# Microcontroller.net
KiCad netlist of a schematic drawn in Altium Designer
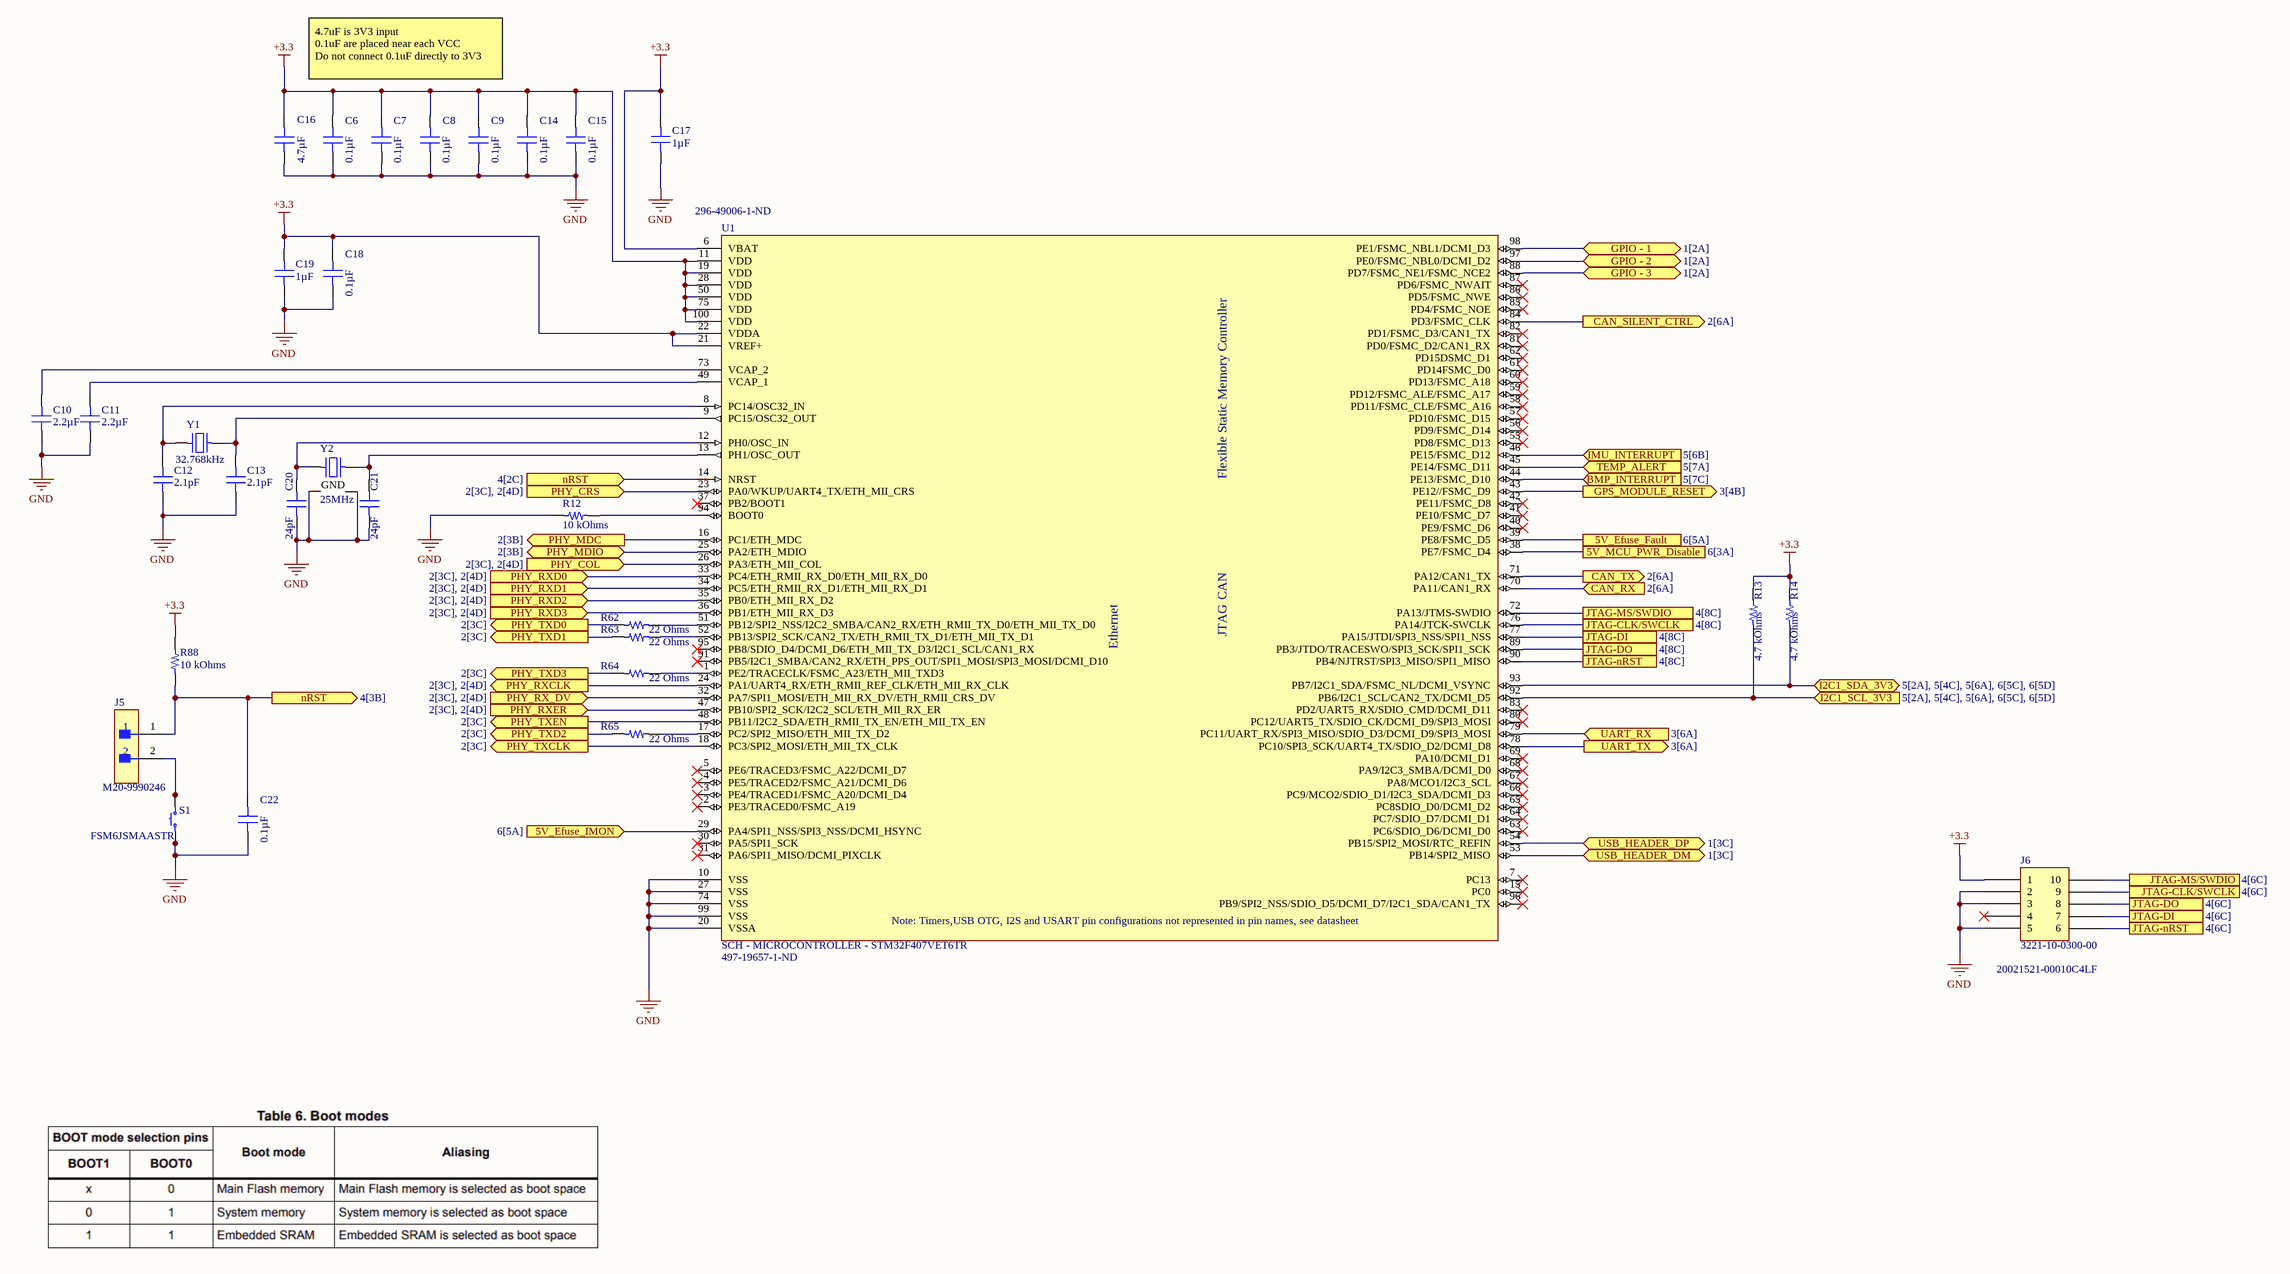
[diagram p0: Microcontroller.SchDoc]

(export (version "E")
  (design (tool "Eeschema 10.0.6"))
  (components
    (comp (ref "C6")
      (value "0.1µF")
      (footprint "CAP 0603_1608")
      (description "CAP CER 0.1UF 25V X7R 0603")
      (fields
        (field (name "PART NUMBER") "CL10B104KA8WPNC")
        (field (name "MANUFACTURER") "Samsung Electro-Mechanics")
      )
      (libsource (lib "Celestial Altium Library - altium_library") (part "Capacitor"))
    )
    (comp (ref "C7")
      (value "0.1µF")
      (footprint "CAP 0603_1608")
      (description "CAP CER 0.1UF 25V X7R 0603")
      (fields
        (field (name "PART NUMBER") "CL10B104KA8WPNC")
        (field (name "MANUFACTURER") "Samsung Electro-Mechanics")
      )
      (libsource (lib "Celestial Altium Library - altium_library") (part "Capacitor"))
    )
    (comp (ref "C8")
      (value "0.1µF")
      (footprint "CAP 0603_1608")
      (description "CAP CER 0.1UF 25V X7R 0603")
      (fields
        (field (name "PART NUMBER") "CL10B104KA8WPNC")
        (field (name "MANUFACTURER") "Samsung Electro-Mechanics")
      )
      (libsource (lib "Celestial Altium Library - altium_library") (part "Capacitor"))
    )
    (comp (ref "C9")
      (value "0.1µF")
      (footprint "CAP 0603_1608")
      (description "CAP CER 0.1UF 25V X7R 0603")
      (fields
        (field (name "PART NUMBER") "CL10B104KA8WPNC")
        (field (name "MANUFACTURER") "Samsung Electro-Mechanics")
      )
      (libsource (lib "Celestial Altium Library - altium_library") (part "Capacitor"))
    )
    (comp (ref "C10")
      (value "2.2µF")
      (footprint "CAP 0603_1608")
      (description "CAP CER 2.2UF 16V X5R 0603")
      (fields (field (name "PART NUMBER") "EMK107BJ225KA-T") (field (name "MANUFACTURER") "Taiyo Yuden"))
      (libsource (lib "Celestial Altium Library - altium_library") (part "Capacitor"))
    )
    (comp (ref "C11")
      (value "2.2µF")
      (footprint "CAP 0603_1608")
      (description "CAP CER 2.2UF 16V X5R 0603")
      (fields (field (name "PART NUMBER") "EMK107BJ225KA-T") (field (name "MANUFACTURER") "Taiyo Yuden"))
      (libsource (lib "Celestial Altium Library - altium_library") (part "Capacitor"))
    )
    (comp (ref "C12")
      (value "2.1pF")
      (footprint "CAP 0603_1608")
      (description "CAP CER RF 2.1PF 50V +/-0.1 PF C")
      (fields (field (name "PART NUMBER") "CBR06C219B5GAC") (field (name "MANUFACTURER") "KEMET"))
      (libsource (lib "Celestial Altium Library - altium_library") (part "Capacitor"))
    )
    (comp (ref "C13")
      (value "2.1pF")
      (footprint "CAP 0603_1608")
      (description "CAP CER RF 2.1PF 50V +/-0.1 PF C")
      (fields (field (name "PART NUMBER") "CBR06C219B5GAC") (field (name "MANUFACTURER") "KEMET"))
      (libsource (lib "Celestial Altium Library - altium_library") (part "Capacitor"))
    )
    (comp (ref "C14")
      (value "0.1µF")
      (footprint "CAP 0603_1608")
      (description "CAP CER 0.1UF 25V X7R 0603")
      (fields
        (field (name "PART NUMBER") "CL10B104KA8WPNC")
        (field (name "MANUFACTURER") "Samsung Electro-Mechanics")
      )
      (libsource (lib "Celestial Altium Library - altium_library") (part "Capacitor"))
    )
    (comp (ref "C15")
      (value "0.1µF")
      (footprint "CAP 0603_1608")
      (description "CAP CER 0.1UF 25V X7R 0603")
      (fields
        (field (name "PART NUMBER") "CL10B104KA8WPNC")
        (field (name "MANUFACTURER") "Samsung Electro-Mechanics")
      )
      (libsource (lib "Celestial Altium Library - altium_library") (part "Capacitor"))
    )
    (comp (ref "C16")
      (value "4.7µF")
      (footprint "CAP 0603_1608")
      (description "CAP CER 4.7UF 16V X5R 0603")
      (fields
        (field (name "PART NUMBER") "C1608X5R1C475K080AC")
        (field (name "MANUFACTURER") "TDK Corporation")
      )
      (libsource (lib "Celestial Altium Library - altium_library") (part "Capacitor"))
    )
    (comp (ref "C17")
      (value "1µF")
      (footprint "CAP 0603_1608")
      (description "CAP CER 1UF 16V X7R 0603")
      (fields
        (field (name "PART NUMBER") "GCM188R71C105KA64J")
        (field (name "MANUFACTURER") "Murata Electronics")
      )
      (libsource (lib "Celestial Altium Library - altium_library") (part "Capacitor"))
    )
    (comp (ref "C18")
      (value "0.1µF")
      (footprint "CAP 0603_1608")
      (description "CAP CER 0.1UF 25V X7R 0603")
      (fields
        (field (name "PART NUMBER") "CL10B104KA8WPNC")
        (field (name "MANUFACTURER") "Samsung Electro-Mechanics")
      )
      (libsource (lib "Celestial Altium Library - altium_library") (part "Capacitor"))
    )
    (comp (ref "C19")
      (value "1µF")
      (footprint "CAP 0603_1608")
      (description "CAP CER 1UF 16V X7R 0603")
      (fields
        (field (name "PART NUMBER") "GCM188R71C105KA64J")
        (field (name "MANUFACTURER") "Murata Electronics")
      )
      (libsource (lib "Celestial Altium Library - altium_library") (part "Capacitor"))
    )
    (comp (ref "C20")
      (value "24pF")
      (footprint "CAP 0603_1608")
      (description "CAP CER 24PF 50V C0G/NP0 0603")
      (fields
        (field (name "PART NUMBER") "CL10C240JB8NNNC")
        (field (name "MANUFACTURER") "Samsung Electro-Mechanics")
      )
      (libsource (lib "Celestial Altium Library - altium_library") (part "Capacitor"))
    )
    (comp (ref "C21")
      (value "24pF")
      (footprint "CAP 0603_1608")
      (description "CAP CER 24PF 50V C0G/NP0 0603")
      (fields
        (field (name "PART NUMBER") "CL10C240JB8NNNC")
        (field (name "MANUFACTURER") "Samsung Electro-Mechanics")
      )
      (libsource (lib "Celestial Altium Library - altium_library") (part "Capacitor"))
    )
    (comp (ref "C22")
      (value "0.1µF")
      (footprint "CAP 0603_1608")
      (description "CAP CER 0.1UF 25V X7R 0603")
      (fields
        (field (name "PART NUMBER") "CL10B104KA8WPNC")
        (field (name "MANUFACTURER") "Samsung Electro-Mechanics")
      )
      (libsource (lib "Celestial Altium Library - altium_library") (part "Capacitor"))
    )
    (comp (ref "J5")
      (value "M20-9990246")
      (footprint "FP-M20-9990246-MFG")
      (description "CONN HEADER VERT 2POS 2.54MM")
      (fields
        (field (name "OCTOPART") "https://octopart.com/m20-9990246-harwin-2590635")
        (field (name "MANUFACTURER") "Harwin")
      )
      (libsource (lib "Altium Content Vault") (part "3bc925449376181038e59eaffc5286c"))
    )
    (comp (ref "J6")
      (value "3221-10-0300-00")
      (footprint "CNC TECH 3221-10-0300-00")
      (description "CONN HEADER SMD 10POS 1.27MM")
      (fields (field (name "MANUFACTURER") "CNC Tech"))
      (libsource (lib "Celestial Altium Library - altium_library") (part "2x5 Pin"))
    )
    (comp (ref "R12")
      (value "10 kOhms")
      (footprint "RES 0603_1608")
      (description "RES 10K OHM 5% 1/10W 0603")
      (fields
        (field (name "PART NUMBER") "RMCF0603JT10K0")
        (field (name "MANUFACTURER") "Stackpole Electronics Inc")
      )
      (libsource (lib "Celestial Altium Library - altium_library") (part "Resistor"))
    )
    (comp (ref "R13")
      (value "4.7 kOhms")
      (footprint "RES 0603_1608")
      (description "RES 4.7K OHM 1% 1/10W 0603")
      (fields
        (field (name "PART NUMBER") "RMCF0603FT4K70")
        (field (name "MANUFACTURER") "Stackpole Electronics Inc")
      )
      (libsource (lib "Celestial Altium Library - altium_library") (part "Resistor"))
    )
    (comp (ref "R14")
      (value "4.7 kOhms")
      (footprint "RES 0603_1608")
      (description "RES 4.7K OHM 1% 1/10W 0603")
      (fields
        (field (name "PART NUMBER") "RMCF0603FT4K70")
        (field (name "MANUFACTURER") "Stackpole Electronics Inc")
      )
      (libsource (lib "Celestial Altium Library - altium_library") (part "Resistor"))
    )
    (comp (ref "R62")
      (value "22 Ohms")
      (footprint "RES 0603_1608")
      (description "RES 22 OHM 1% 1/10W 0603")
      (fields
        (field (name "PART NUMBER") "RMCF0603FT22R0")
        (field (name "MANUFACTURER") "Stackpole Electronics Inc")
      )
      (libsource (lib "Celestial Altium Library - altium_library") (part "Resistor"))
    )
    (comp (ref "R63")
      (value "22 Ohms")
      (footprint "RES 0603_1608")
      (description "RES 22 OHM 1% 1/10W 0603")
      (fields
        (field (name "PART NUMBER") "RMCF0603FT22R0")
        (field (name "MANUFACTURER") "Stackpole Electronics Inc")
      )
      (libsource (lib "Celestial Altium Library - altium_library") (part "Resistor"))
    )
    (comp (ref "R64")
      (value "22 Ohms")
      (footprint "RES 0603_1608")
      (description "RES 22 OHM 1% 1/10W 0603")
      (fields
        (field (name "PART NUMBER") "RMCF0603FT22R0")
        (field (name "MANUFACTURER") "Stackpole Electronics Inc")
      )
      (libsource (lib "Celestial Altium Library - altium_library") (part "Resistor"))
    )
    (comp (ref "R65")
      (value "22 Ohms")
      (footprint "RES 0603_1608")
      (description "RES 22 OHM 1% 1/10W 0603")
      (fields
        (field (name "PART NUMBER") "RMCF0603FT22R0")
        (field (name "MANUFACTURER") "Stackpole Electronics Inc")
      )
      (libsource (lib "Celestial Altium Library - altium_library") (part "Resistor"))
    )
    (comp (ref "R88")
      (value "10 kOhms")
      (footprint "RES 0603_1608")
      (description "RES 10K OHM 5% 1/10W 0603")
      (fields
        (field (name "PART NUMBER") "RMCF0603JT10K0")
        (field (name "MANUFACTURER") "Stackpole Electronics Inc")
      )
      (libsource (lib "Celestial Altium Library - altium_library") (part "Resistor"))
    )
    (comp (ref "S1")
      (value "FSM6JSMAASTR")
      (footprint "TE FSM6JSMA")
      (description "SWITCH TACTILE SPST-NO 0.05A 24V")
      (fields (field (name "MANUFACTURER") "TE Connectivity ALCOSWITCH Switches"))
      (libsource (lib "Celestial Altium Library - altium_library") (part "SPST-NO 4 PIN"))
    )
    (comp (ref "U1")
      (value "SCH - MICROCONTROLLER - STM32F407VET6TR")
      (footprint "PCB - LEADLESS - QFP - ST LQFP-100 14X14MM")
      (fields (field (name "SUPPLIER PART NUMBER 1") "497-19657-1-ND"))
      (libsource (lib "HAB_ICs") (part "SCH - MICROCONTROLLER - STM32F407VET6TR"))
    )
    (comp (ref "Y1")
      (value "32.768kHz")
      (footprint "ABRACON ABS07")
      (description "IOT 32.786KHZ XTAL")
      (fields
        (field (name "PART NUMBER") "ABS07-166-32.768KHZ-T")
        (field (name "MANUFACTURER") "Abracon LLC")
      )
      (libsource (lib "Celestial Altium Library - altium_library") (part "Abracon Crystal ABS07"))
    )
    (comp (ref "Y2")
      (value "25MHz")
      (footprint "EPSON TSX-3225")
      (description "CRYSTAL 25.0000MHZ 18PF SMD")
      (fields (field (name "PART NUMBER") "TSX-3225 25.0000MF20P-C0") (field (name "MANUFACTURER") "EPSON"))
      (libsource (lib "Celestial Altium Library - altium_library") (part "Epson Crystal TSX-3225"))
    )
  )
  (nets
    (net (code "1") (name "+3.3") (class "Default")
      (node (ref "C14") (pin "2") (pinfunction "2_2") (pintype "passive"))
      (node (ref "C15") (pin "2") (pinfunction "2_2") (pintype "passive"))
      (node (ref "C16") (pin "2") (pinfunction "2_2") (pintype "passive"))
      (node (ref "C17") (pin "2") (pinfunction "2_2") (pintype "passive"))
      (node (ref "C18") (pin "2") (pinfunction "2_2") (pintype "passive"))
      (node (ref "C19") (pin "2") (pinfunction "2_2") (pintype "passive"))
      (node (ref "C6") (pin "2") (pinfunction "2_2") (pintype "passive"))
      (node (ref "C7") (pin "2") (pinfunction "2_2") (pintype "passive"))
      (node (ref "C8") (pin "2") (pinfunction "2_2") (pintype "passive"))
      (node (ref "C9") (pin "2") (pinfunction "2_2") (pintype "passive"))
      (node (ref "J6") (pin "1") (pinfunction "1_1") (pintype "passive"))
      (node (ref "R13") (pin "2") (pinfunction "2_2") (pintype "passive"))
      (node (ref "R14") (pin "2") (pinfunction "2_2") (pintype "passive"))
      (node (ref "R88") (pin "1") (pinfunction "1_1") (pintype "passive"))
      (node (ref "U1") (pin "100") (pinfunction "VDD_100") (pintype "power_in"))
      (node (ref "U1") (pin "11") (pinfunction "VDD_11") (pintype "power_in"))
      (node (ref "U1") (pin "19") (pinfunction "VDD_19") (pintype "power_in"))
      (node (ref "U1") (pin "21") (pinfunction "VREF+_21") (pintype "power_in"))
      (node (ref "U1") (pin "22") (pinfunction "VDDA_22") (pintype "power_in"))
      (node (ref "U1") (pin "28") (pinfunction "VDD_28") (pintype "power_in"))
      (node (ref "U1") (pin "50") (pinfunction "VDD_50") (pintype "power_in"))
      (node (ref "U1") (pin "6") (pinfunction "VBAT_6") (pintype "power_in"))
      (node (ref "U1") (pin "75") (pinfunction "VDD_75") (pintype "power_in"))
    )
    (net (code "2") (name "/5V_Efuse_Fault") (class "Default")
      (node (ref "U1") (pin "39") (pinfunction "PE8/FSMC_D5_39") (pintype "bidirectional"))
    )
    (net (code "3") (name "/5V_Efuse_IMON") (class "Default")
      (node (ref "U1") (pin "29") (pinfunction "PA4/SPI1_NSS/SPI3_NSS/DCMI_HSYNC_29") (pintype "bidirectional"))
    )
    (net (code "4") (name "/5V_MCU_PWR_Disable") (class "Default")
      (node (ref "U1") (pin "38") (pinfunction "PE7/FSMC_D4_38") (pintype "bidirectional"))
    )
    (net (code "5") (name "/BMP_INTERRUPT") (class "Default")
      (node (ref "U1") (pin "44") (pinfunction "PE13/FSMC_D10_44") (pintype "bidirectional"))
    )
    (net (code "6") (name "/CAN_RX") (class "Default")
      (node (ref "U1") (pin "70") (pinfunction "PA11/CAN1_RX_70") (pintype "bidirectional"))
    )
    (net (code "7") (name "/CAN_SILENT_CTRL") (class "Default")
      (node (ref "U1") (pin "84") (pinfunction "PD3/FSMC_CLK_84") (pintype "bidirectional"))
    )
    (net (code "8") (name "/CAN_TX") (class "Default")
      (node (ref "U1") (pin "71") (pinfunction "PA12/CAN1_TX_71") (pintype "bidirectional"))
    )
    (net (code "9") (name "/GPIO - 1") (class "Default")
      (node (ref "U1") (pin "98") (pinfunction "PE1/FSMC_NBL1/DCMI_D3_98") (pintype "bidirectional"))
    )
    (net (code "10") (name "/GPIO - 2") (class "Default")
      (node (ref "U1") (pin "97") (pinfunction "PE0/FSMC_NBL0/DCMI_D2_97") (pintype "bidirectional"))
    )
    (net (code "11") (name "/GPIO - 3") (class "Default")
      (node (ref "U1") (pin "88") (pinfunction "PD7/FSMC_NE1/FSMC_NCE2_88") (pintype "bidirectional"))
    )
    (net (code "12") (name "/GPS_MODULE_RESET") (class "Default")
      (node (ref "U1") (pin "43") (pinfunction "PE12//FSMC_D9_43") (pintype "bidirectional"))
    )
    (net (code "13") (name "/I2C1_SCL_3V3") (class "Default")
      (node (ref "R13") (pin "1") (pinfunction "1_1") (pintype "passive"))
      (node (ref "U1") (pin "92") (pinfunction "PB6/I2C1_SCL/CAN2_TX/DCMI_D5_92") (pintype "bidirectional"))
    )
    (net (code "14") (name "/I2C1_SDA_3V3") (class "Default")
      (node (ref "R14") (pin "1") (pinfunction "1_1") (pintype "passive"))
      (node (ref "U1") (pin "93") (pinfunction "PB7/I2C1_SDA/FSMC_NL/DCMI_VSYNC_93") (pintype "bidirectional"))
    )
    (net (code "15") (name "/IMU_INTERRUPT") (class "Default")
      (node (ref "U1") (pin "46") (pinfunction "PE15/FSMC_D12_46") (pintype "bidirectional"))
    )
    (net (code "16") (name "/JTAG-CLK{slash}SWCLK") (class "Default")
      (node (ref "J6") (pin "9") (pinfunction "9_9") (pintype "passive"))
      (node (ref "U1") (pin "76") (pinfunction "PA14/JTCK-SWCLK_76") (pintype "bidirectional"))
    )
    (net (code "17") (name "/JTAG-DI") (class "Default")
      (node (ref "J6") (pin "7") (pinfunction "7_7") (pintype "passive"))
      (node (ref "U1") (pin "77") (pinfunction "PA15/JTDI/SPI3_NSS/SPI1_NSS_77") (pintype "bidirectional"))
    )
    (net (code "18") (name "/JTAG-DO") (class "Default")
      (node (ref "J6") (pin "8") (pinfunction "8_8") (pintype "passive"))
      (node (ref "U1") (pin "89") (pinfunction "PB3/JTDO/TRACESWO/SPI3_SCK/SPI1_SCK_89") (pintype "bidirectional"))
    )
    (net (code "19") (name "/JTAG-MS{slash}SWDIO") (class "Default")
      (node (ref "J6") (pin "10") (pinfunction "10_10") (pintype "passive"))
      (node (ref "U1") (pin "72") (pinfunction "PA13/JTMS-SWDIO_72") (pintype "bidirectional"))
    )
    (net (code "20") (name "/JTAG-nRST") (class "Default")
      (node (ref "J6") (pin "6") (pinfunction "6_6") (pintype "passive"))
      (node (ref "U1") (pin "90") (pinfunction "PB4/NJTRST/SPI3_MISO/SPI1_MISO_90") (pintype "bidirectional"))
    )
    (net (code "21") (name "/PHY_COL") (class "Default")
      (node (ref "U1") (pin "26") (pinfunction "PA3/ETH_MII_COL_26") (pintype "bidirectional"))
    )
    (net (code "22") (name "/PHY_CRS") (class "Default")
      (node (ref "U1") (pin "23") (pinfunction "PA0/WKUP/UART4_TX/ETH_MII_CRS_23") (pintype "bidirectional"))
    )
    (net (code "23") (name "/PHY_MDC") (class "Default")
      (node (ref "U1") (pin "16") (pinfunction "PC1/ETH_MDC_16") (pintype "bidirectional"))
    )
    (net (code "24") (name "/PHY_MDIO") (class "Default")
      (node (ref "U1") (pin "25") (pinfunction "PA2/ETH_MDIO_25") (pintype "bidirectional"))
    )
    (net (code "25") (name "/PHY_RXCLK") (class "Default")
      (node (ref "U1") (pin "24") (pinfunction "PA1/UART4_RX/ETH_RMII_REF_CLK/ETH_MII_RX_CLK_24") (pintype "bidirectional"))
    )
    (net (code "26") (name "/PHY_RXD0") (class "Default")
      (node (ref "U1") (pin "33") (pinfunction "PC4/ETH_RMII_RX_D0/ETH_MII_RX_D0_33") (pintype "bidirectional"))
    )
    (net (code "27") (name "/PHY_RXD1") (class "Default")
      (node (ref "U1") (pin "34") (pinfunction "PC5/ETH_RMII_RX_D1/ETH_MII_RX_D1_34") (pintype "bidirectional"))
    )
    (net (code "28") (name "/PHY_RXD2") (class "Default")
      (node (ref "U1") (pin "35") (pinfunction "PB0/ETH_MII_RX_D2_35") (pintype "bidirectional"))
    )
    (net (code "29") (name "/PHY_RXD3") (class "Default")
      (node (ref "U1") (pin "36") (pinfunction "PB1/ETH_MII_RX_D3_36") (pintype "bidirectional"))
    )
    (net (code "30") (name "/PHY_RXER") (class "Default")
      (node (ref "U1") (pin "47") (pinfunction "PB10/SPI2_SCK/I2C2_SCL/ETH_MII_RX_ER_47") (pintype "bidirectional"))
    )
    (net (code "31") (name "/PHY_RX_DV") (class "Default")
      (node (ref "U1") (pin "32") (pinfunction "PA7/SPI1_MOSI/ETH_MII_RX_DV/ETH_RMII_CRS_DV_32") (pintype "bidirectional"))
    )
    (net (code "32") (name "/PHY_TXCLK") (class "Default")
      (node (ref "U1") (pin "18") (pinfunction "PC3/SPI2_MOSI/ETH_MII_TX_CLK_18") (pintype "bidirectional"))
    )
    (net (code "33") (name "/PHY_TXD0") (class "Default")
      (node (ref "R62") (pin "1") (pinfunction "1_1") (pintype "passive"))
    )
    (net (code "34") (name "/PHY_TXD1") (class "Default")
      (node (ref "R63") (pin "1") (pinfunction "1_1") (pintype "passive"))
    )
    (net (code "35") (name "/PHY_TXD2") (class "Default")
      (node (ref "R65") (pin "1") (pinfunction "1_1") (pintype "passive"))
    )
    (net (code "36") (name "/PHY_TXD3") (class "Default")
      (node (ref "R64") (pin "1") (pinfunction "1_1") (pintype "passive"))
    )
    (net (code "37") (name "/PHY_TXEN") (class "Default")
      (node (ref "U1") (pin "48") (pinfunction "PB11/I2C2_SDA/ETH_RMII_TX_EN/ETH_MII_TX_EN_48") (pintype "bidirectional"))
    )
    (net (code "38") (name "/TEMP_ALERT") (class "Default")
      (node (ref "U1") (pin "45") (pinfunction "PE14/FSMC_D11_45") (pintype "bidirectional"))
    )
    (net (code "39") (name "/UART_RX") (class "Default")
      (node (ref "U1") (pin "79") (pinfunction "PC11/UART_RX/SPI3_MISO/SDIO_D3/DCMI_D9/SPI3_MOSI_79") (pintype "bidirectional"))
    )
    (net (code "40") (name "/UART_TX") (class "Default")
      (node (ref "U1") (pin "78") (pinfunction "PC10/SPI3_SCK/UART4_TX/SDIO_D2/DCMI_D8_78") (pintype "bidirectional"))
    )
    (net (code "41") (name "/USB_HEADER_DM") (class "Default")
      (node (ref "U1") (pin "53") (pinfunction "PB14/SPI2_MISO_53") (pintype "bidirectional"))
    )
    (net (code "42") (name "/USB_HEADER_DP") (class "Default")
      (node (ref "U1") (pin "54") (pinfunction "PB15/SPI2_MOSI/RTC_REFIN_54") (pintype "bidirectional"))
    )
    (net (code "43") (name "/nRST") (class "Default")
      (node (ref "C22") (pin "2") (pinfunction "2_2") (pintype "passive"))
      (node (ref "J5") (pin "1") (pinfunction "1_1") (pintype "passive"))
      (node (ref "R88") (pin "2") (pinfunction "2_2") (pintype "passive"))
      (node (ref "U1") (pin "14") (pinfunction "NRST_14") (pintype "input"))
    )
    (net (code "44") (name "GND") (class "Default")
      (node (ref "C10") (pin "1") (pinfunction "1_1") (pintype "passive"))
      (node (ref "C11") (pin "1") (pinfunction "1_1") (pintype "passive"))
      (node (ref "C12") (pin "1") (pinfunction "1_1") (pintype "passive"))
      (node (ref "C13") (pin "1") (pinfunction "1_1") (pintype "passive"))
      (node (ref "C14") (pin "1") (pinfunction "1_1") (pintype "passive"))
      (node (ref "C15") (pin "1") (pinfunction "1_1") (pintype "passive"))
      (node (ref "C16") (pin "1") (pinfunction "1_1") (pintype "passive"))
      (node (ref "C17") (pin "1") (pinfunction "1_1") (pintype "passive"))
      (node (ref "C18") (pin "1") (pinfunction "1_1") (pintype "passive"))
      (node (ref "C19") (pin "1") (pinfunction "1_1") (pintype "passive"))
      (node (ref "C20") (pin "1") (pinfunction "1_1") (pintype "passive"))
      (node (ref "C21") (pin "1") (pinfunction "1_1") (pintype "passive"))
      (node (ref "C22") (pin "1") (pinfunction "1_1") (pintype "passive"))
      (node (ref "C6") (pin "1") (pinfunction "1_1") (pintype "passive"))
      (node (ref "C7") (pin "1") (pinfunction "1_1") (pintype "passive"))
      (node (ref "C8") (pin "1") (pinfunction "1_1") (pintype "passive"))
      (node (ref "C9") (pin "1") (pinfunction "1_1") (pintype "passive"))
      (node (ref "J6") (pin "2") (pinfunction "2_2") (pintype "passive"))
      (node (ref "J6") (pin "3") (pinfunction "3_3") (pintype "passive"))
      (node (ref "J6") (pin "5") (pinfunction "5_5") (pintype "passive"))
      (node (ref "R12") (pin "2") (pinfunction "2_2") (pintype "passive"))
      (node (ref "S1") (pin "1") (pinfunction "1_1") (pintype "passive"))
      (node (ref "S1") (pin "2") (pinfunction "2_2") (pintype "passive"))
      (node (ref "U1") (pin "10") (pinfunction "VSS_10") (pintype "power_in"))
      (node (ref "U1") (pin "20") (pinfunction "VSSA_20") (pintype "power_in"))
      (node (ref "U1") (pin "27") (pinfunction "VSS_27") (pintype "power_in"))
      (node (ref "U1") (pin "74") (pinfunction "VSS_74") (pintype "power_in"))
      (node (ref "U1") (pin "99") (pinfunction "VSS_99") (pintype "power_in"))
      (node (ref "Y2") (pin "2") (pinfunction "GND_2") (pintype "passive"))
      (node (ref "Y2") (pin "4") (pinfunction "GND_4") (pintype "passive"))
    )
    (net (code "45") (name "Net-(J5-Pad2)") (class "Default")
      (node (ref "J5") (pin "2") (pinfunction "2_2") (pintype "passive"))
      (node (ref "S1") (pin "3") (pinfunction "3_3") (pintype "passive"))
      (node (ref "S1") (pin "4") (pinfunction "4_4") (pintype "passive"))
    )
    (net (code "46") (name "Net-(U1-BOOT0)") (class "Default")
      (node (ref "R12") (pin "1") (pinfunction "1_1") (pintype "passive"))
      (node (ref "U1") (pin "94") (pinfunction "BOOT0_94") (pintype "bidirectional"))
    )
    (net (code "47") (name "Net-(U1-PB12{slash}SPI2_NSS{slash}I2C2_SMBA{slash}CAN2_RX{slash}ETH_RMII_TX_D0{slash}ETH_MII_TX_D0)") (class "Default")
      (node (ref "R62") (pin "2") (pinfunction "2_2") (pintype "passive"))
      (node (ref "U1") (pin "51") (pinfunction "PB12/SPI2_NSS/I2C2_SMBA/CAN2_RX/ETH_RMII_TX_D0/ETH_MII_TX_D0_51") (pintype "bidirectional"))
    )
    (net (code "48") (name "Net-(U1-PB13{slash}SPI2_SCK{slash}CAN2_TX{slash}ETH_RMII_TX_D1{slash}ETH_MII_TX_D1)") (class "Default")
      (node (ref "R63") (pin "2") (pinfunction "2_2") (pintype "passive"))
      (node (ref "U1") (pin "52") (pinfunction "PB13/SPI2_SCK/CAN2_TX/ETH_RMII_TX_D1/ETH_MII_TX_D1_52") (pintype "bidirectional"))
    )
    (net (code "49") (name "Net-(U1-PC2{slash}SPI2_MISO{slash}ETH_MII_TX_D2)") (class "Default")
      (node (ref "R65") (pin "2") (pinfunction "2_2") (pintype "passive"))
      (node (ref "U1") (pin "17") (pinfunction "PC2/SPI2_MISO/ETH_MII_TX_D2_17") (pintype "bidirectional"))
    )
    (net (code "50") (name "Net-(U1-PC14{slash}OSC32_IN)") (class "Default")
      (node (ref "C12") (pin "2") (pinfunction "2_2") (pintype "passive"))
      (node (ref "U1") (pin "8") (pinfunction "PC14/OSC32_IN_8") (pintype "input"))
      (node (ref "Y1") (pin "1") (pinfunction "1_1") (pintype "passive"))
    )
    (net (code "51") (name "Net-(U1-PC15{slash}OSC32_OUT)") (class "Default")
      (node (ref "C13") (pin "2") (pinfunction "2_2") (pintype "passive"))
      (node (ref "U1") (pin "9") (pinfunction "PC15/OSC32_OUT_9") (pintype "output"))
      (node (ref "Y1") (pin "2") (pinfunction "2_2") (pintype "passive"))
    )
    (net (code "52") (name "Net-(U1-PE2{slash}TRACECLK{slash}FSMC_A23{slash}ETH_MII_TXD3)") (class "Default")
      (node (ref "R64") (pin "2") (pinfunction "2_2") (pintype "passive"))
      (node (ref "U1") (pin "1") (pinfunction "PE2/TRACECLK/FSMC_A23/ETH_MII_TXD3_1") (pintype "bidirectional"))
    )
    (net (code "53") (name "Net-(U1-PH0{slash}OSC_IN)") (class "Default")
      (node (ref "C20") (pin "2") (pinfunction "2_2") (pintype "passive"))
      (node (ref "U1") (pin "12") (pinfunction "PH0/OSC_IN_12") (pintype "input"))
      (node (ref "Y2") (pin "1") (pinfunction "1_1") (pintype "passive"))
    )
    (net (code "54") (name "Net-(U1-PH1{slash}OSC_OUT)") (class "Default")
      (node (ref "C21") (pin "2") (pinfunction "2_2") (pintype "passive"))
      (node (ref "U1") (pin "13") (pinfunction "PH1/OSC_OUT_13") (pintype "output"))
      (node (ref "Y2") (pin "3") (pinfunction "3_3") (pintype "passive"))
    )
    (net (code "55") (name "Net-(U1-VCAP_1)") (class "Default")
      (node (ref "C11") (pin "2") (pinfunction "2_2") (pintype "passive"))
      (node (ref "U1") (pin "49") (pinfunction "VCAP_1_49") (pintype "power_in"))
    )
    (net (code "56") (name "Net-(U1-VCAP_2)") (class "Default")
      (node (ref "C10") (pin "2") (pinfunction "2_2") (pintype "passive"))
      (node (ref "U1") (pin "73") (pinfunction "VCAP_2_73") (pintype "power_in"))
    )
    (net (code "57") (name "unconnected-(J6-Pad4)") (class "Default")
      (node (ref "J6") (pin "4") (pinfunction "4_4") (pintype "passive+no_connect"))
    )
    (net (code "58") (name "unconnected-(U1-PA5{slash}SPI1_SCK-Pad30)") (class "Default")
      (node (ref "U1") (pin "30") (pinfunction "PA5/SPI1_SCK_30") (pintype "bidirectional+no_connect"))
    )
    (net (code "59") (name "unconnected-(U1-PA6{slash}SPI1_MISO{slash}DCMI_PIXCLK-Pad31)") (class "Default")
      (node (ref "U1") (pin "31") (pinfunction "PA6/SPI1_MISO/DCMI_PIXCLK_31") (pintype "bidirectional+no_connect"))
    )
    (net (code "60") (name "unconnected-(U1-PA8{slash}MCO1{slash}I2C3_SCL-Pad67)") (class "Default")
      (node (ref "U1") (pin "67") (pinfunction "PA8/MCO1/I2C3_SCL_67") (pintype "bidirectional+no_connect"))
    )
    (net (code "61") (name "unconnected-(U1-PA9{slash}I2C3_SMBA{slash}DCMI_D0-Pad68)") (class "Default")
      (node (ref "U1") (pin "68") (pinfunction "PA9/I2C3_SMBA/DCMI_D0_68") (pintype "bidirectional+no_connect"))
    )
    (net (code "62") (name "unconnected-(U1-PA10{slash}DCMI_D1-Pad69)") (class "Default")
      (node (ref "U1") (pin "69") (pinfunction "PA10/DCMI_D1_69") (pintype "bidirectional+no_connect"))
    )
    (net (code "63") (name "unconnected-(U1-PB2{slash}BOOT1-Pad37)") (class "Default")
      (node (ref "U1") (pin "37") (pinfunction "PB2/BOOT1_37") (pintype "bidirectional+no_connect"))
    )
    (net (code "64") (name "unconnected-(U1-PB5{slash}I2C1_SMBA{slash}CAN2_RX{slash}ETH_PPS_OUT{slash}SPI1_MOSI{slash}SPI3_MOSI{slash}DCMI_D10-Pad91)") (class "Default")
      (node (ref "U1") (pin "91") (pinfunction "PB5/I2C1_SMBA/CAN2_RX/ETH_PPS_OUT/SPI1_MOSI/SPI3_MOSI/DCMI_D10_91") (pintype "bidirectional+no_connect"))
    )
    (net (code "65") (name "unconnected-(U1-PB8{slash}SDIO_D4{slash}DCMI_D6{slash}ETH_MII_TX_D3{slash}I2C1_SCL{slash}CAN1_RX-Pad95)") (class "Default")
      (node (ref "U1") (pin "95") (pinfunction "PB8/SDIO_D4/DCMI_D6/ETH_MII_TX_D3/I2C1_SCL/CAN1_RX_95") (pintype "bidirectional+no_connect"))
    )
    (net (code "66") (name "unconnected-(U1-PB9{slash}SPI2_NSS{slash}SDIO_D5{slash}DCMI_D7{slash}I2C1_SDA{slash}CAN1_TX-Pad96)") (class "Default")
      (node (ref "U1") (pin "96") (pinfunction "PB9/SPI2_NSS/SDIO_D5/DCMI_D7/I2C1_SDA/CAN1_TX_96") (pintype "bidirectional+no_connect"))
    )
    (net (code "67") (name "unconnected-(U1-PC0-Pad15)") (class "Default")
      (node (ref "U1") (pin "15") (pinfunction "PC0_15") (pintype "bidirectional+no_connect"))
    )
    (net (code "68") (name "unconnected-(U1-PC6{slash}SDIO_D6{slash}DCMI_D0-Pad63)") (class "Default")
      (node (ref "U1") (pin "63") (pinfunction "PC6/SDIO_D6/DCMI_D0_63") (pintype "bidirectional+no_connect"))
    )
    (net (code "69") (name "unconnected-(U1-PC7{slash}SDIO_D7{slash}DCMI_D1-Pad64)") (class "Default")
      (node (ref "U1") (pin "64") (pinfunction "PC7/SDIO_D7/DCMI_D1_64") (pintype "bidirectional+no_connect"))
    )
    (net (code "70") (name "unconnected-(U1-PC8SDIO_D0{slash}DCMI_D2-Pad65)") (class "Default")
      (node (ref "U1") (pin "65") (pinfunction "PC8SDIO_D0/DCMI_D2_65") (pintype "bidirectional+no_connect"))
    )
    (net (code "71") (name "unconnected-(U1-PC9{slash}MCO2{slash}SDIO_D1{slash}I2C3_SDA{slash}DCMI_D3-Pad66)") (class "Default")
      (node (ref "U1") (pin "66") (pinfunction "PC9/MCO2/SDIO_D1/I2C3_SDA/DCMI_D3_66") (pintype "bidirectional+no_connect"))
    )
    (net (code "72") (name "unconnected-(U1-PC12{slash}UART5_TX{slash}SDIO_CK{slash}DCMI_D9{slash}SPI3_MOSI-Pad80)") (class "Default")
      (node (ref "U1") (pin "80") (pinfunction "PC12/UART5_TX/SDIO_CK/DCMI_D9/SPI3_MOSI_80") (pintype "bidirectional+no_connect"))
    )
    (net (code "73") (name "unconnected-(U1-PC13-Pad7)") (class "Default")
      (node (ref "U1") (pin "7") (pinfunction "PC13_7") (pintype "bidirectional+no_connect"))
    )
    (net (code "74") (name "unconnected-(U1-PD0{slash}FSMC_D2{slash}CAN1_RX-Pad81)") (class "Default")
      (node (ref "U1") (pin "81") (pinfunction "PD0/FSMC_D2/CAN1_RX_81") (pintype "bidirectional+no_connect"))
    )
    (net (code "75") (name "unconnected-(U1-PD1{slash}FSMC_D3{slash}CAN1_TX-Pad82)") (class "Default")
      (node (ref "U1") (pin "82") (pinfunction "PD1/FSMC_D3/CAN1_TX_82") (pintype "bidirectional+no_connect"))
    )
    (net (code "76") (name "unconnected-(U1-PD2{slash}UART5_RX{slash}SDIO_CMD{slash}DCMI_D11-Pad83)") (class "Default")
      (node (ref "U1") (pin "83") (pinfunction "PD2/UART5_RX/SDIO_CMD/DCMI_D11_83") (pintype "bidirectional+no_connect"))
    )
    (net (code "77") (name "unconnected-(U1-PD4{slash}FSMC_NOE-Pad85)") (class "Default")
      (node (ref "U1") (pin "85") (pinfunction "PD4/FSMC_NOE_85") (pintype "bidirectional+no_connect"))
    )
    (net (code "78") (name "unconnected-(U1-PD5{slash}FSMC_NWE-Pad86)") (class "Default")
      (node (ref "U1") (pin "86") (pinfunction "PD5/FSMC_NWE_86") (pintype "bidirectional+no_connect"))
    )
    (net (code "79") (name "unconnected-(U1-PD6{slash}FSMC_NWAIT-Pad87)") (class "Default")
      (node (ref "U1") (pin "87") (pinfunction "PD6/FSMC_NWAIT_87") (pintype "bidirectional+no_connect"))
    )
    (net (code "80") (name "unconnected-(U1-PD8{slash}FSMC_D13-Pad55)") (class "Default")
      (node (ref "U1") (pin "55") (pinfunction "PD8/FSMC_D13_55") (pintype "bidirectional+no_connect"))
    )
    (net (code "81") (name "unconnected-(U1-PD9{slash}FSMC_D14-Pad56)") (class "Default")
      (node (ref "U1") (pin "56") (pinfunction "PD9/FSMC_D14_56") (pintype "bidirectional+no_connect"))
    )
    (net (code "82") (name "unconnected-(U1-PD10{slash}FSMC_D15-Pad57)") (class "Default")
      (node (ref "U1") (pin "57") (pinfunction "PD10/FSMC_D15_57") (pintype "bidirectional+no_connect"))
    )
    (net (code "83") (name "unconnected-(U1-PD11{slash}FSMC_CLE{slash}FSMC_A16-Pad58)") (class "Default")
      (node (ref "U1") (pin "58") (pinfunction "PD11/FSMC_CLE/FSMC_A16_58") (pintype "bidirectional+no_connect"))
    )
    (net (code "84") (name "unconnected-(U1-PD12{slash}FSMC_ALE{slash}FSMC_A17-Pad59)") (class "Default")
      (node (ref "U1") (pin "59") (pinfunction "PD12/FSMC_ALE/FSMC_A17_59") (pintype "bidirectional+no_connect"))
    )
    (net (code "85") (name "unconnected-(U1-PD13{slash}FSMC_A18-Pad60)") (class "Default")
      (node (ref "U1") (pin "60") (pinfunction "PD13/FSMC_A18_60") (pintype "bidirectional+no_connect"))
    )
    (net (code "86") (name "unconnected-(U1-PD14FSMC_D0-Pad61)") (class "Default")
      (node (ref "U1") (pin "61") (pinfunction "PD14FSMC_D0_61") (pintype "bidirectional+no_connect"))
    )
    (net (code "87") (name "unconnected-(U1-PD15DSMC_D1-Pad62)") (class "Default")
      (node (ref "U1") (pin "62") (pinfunction "PD15DSMC_D1_62") (pintype "bidirectional+no_connect"))
    )
    (net (code "88") (name "unconnected-(U1-PE3{slash}TRACED0{slash}FSMC_A19-Pad2)") (class "Default")
      (node (ref "U1") (pin "2") (pinfunction "PE3/TRACED0/FSMC_A19_2") (pintype "bidirectional+no_connect"))
    )
    (net (code "89") (name "unconnected-(U1-PE4{slash}TRACED1{slash}FSMC_A20{slash}DCMI_D4-Pad3)") (class "Default")
      (node (ref "U1") (pin "3") (pinfunction "PE4/TRACED1/FSMC_A20/DCMI_D4_3") (pintype "bidirectional+no_connect"))
    )
    (net (code "90") (name "unconnected-(U1-PE5{slash}TRACED2{slash}FSMC_A21{slash}DCMI_D6-Pad4)") (class "Default")
      (node (ref "U1") (pin "4") (pinfunction "PE5/TRACED2/FSMC_A21/DCMI_D6_4") (pintype "bidirectional+no_connect"))
    )
    (net (code "91") (name "unconnected-(U1-PE6{slash}TRACED3{slash}FSMC_A22{slash}DCMI_D7-Pad5)") (class "Default")
      (node (ref "U1") (pin "5") (pinfunction "PE6/TRACED3/FSMC_A22/DCMI_D7_5") (pintype "bidirectional+no_connect"))
    )
    (net (code "92") (name "unconnected-(U1-PE9{slash}FSMC_D6-Pad40)") (class "Default")
      (node (ref "U1") (pin "40") (pinfunction "PE9/FSMC_D6_40") (pintype "bidirectional+no_connect"))
    )
    (net (code "93") (name "unconnected-(U1-PE10{slash}FSMC_D7-Pad41)") (class "Default")
      (node (ref "U1") (pin "41") (pinfunction "PE10/FSMC_D7_41") (pintype "bidirectional+no_connect"))
    )
    (net (code "94") (name "unconnected-(U1-PE11{slash}FSMC_D8-Pad42)") (class "Default")
      (node (ref "U1") (pin "42") (pinfunction "PE11/FSMC_D8_42") (pintype "bidirectional+no_connect"))
    )
  )
)
